# Nusbio_2-MCU-EX.net
KiCad netlist of a schematic drawn in EAGLE
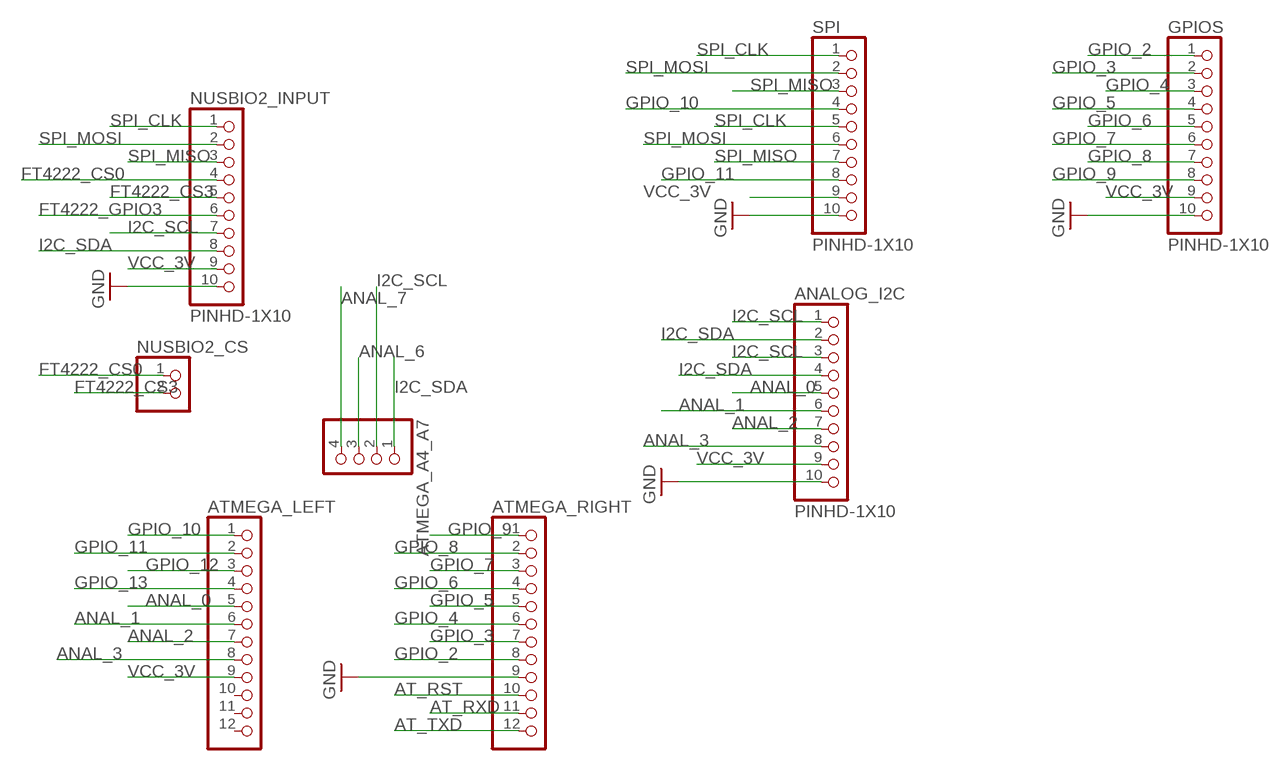
[diagram p0: schematic, sheet 1]

(export (version "E")
  (design (tool "Eeschema 10.0.6"))
  (components
    (comp (ref "ANALOG_I2C")
      (value "PINHD-1X10")
      (footprint "eagle-import:1X10-BIG")
      (libsource (lib "eagle-import") (part "PINHD-1X10"))
    )
    (comp (ref "ATMEGA_A4_A7")
      (value "PINHD-1X4")
      (footprint "eagle-import:1X04")
      (libsource (lib "eagle-import") (part "PINHD-1X4"))
    )
    (comp (ref "ATMEGA_LEFT")
      (value "PINHD-1X12")
      (footprint "eagle-import:1X12")
      (libsource (lib "eagle-import") (part "PINHD-1X12"))
    )
    (comp (ref "ATMEGA_RIGHT")
      (value "PINHD-1X12")
      (footprint "eagle-import:1X12")
      (libsource (lib "eagle-import") (part "PINHD-1X12"))
    )
    (comp (ref "GPIOS")
      (value "PINHD-1X10")
      (footprint "eagle-import:1X10-BIG")
      (libsource (lib "eagle-import") (part "PINHD-1X10"))
    )
    (comp (ref "NUSBIO2_CS")
      (value "PINHD-1X2")
      (footprint "eagle-import:1X02")
      (libsource (lib "eagle-import") (part "PINHD-1X2"))
    )
    (comp (ref "NUSBIO2_INPUT")
      (value "PINHD-1X10")
      (footprint "eagle-import:1X10-BIG")
      (libsource (lib "eagle-import") (part "PINHD-1X10"))
    )
    (comp (ref "SPI")
      (value "PINHD-1X10")
      (footprint "eagle-import:1X10-BIG")
      (libsource (lib "eagle-import") (part "PINHD-1X10"))
    )
  )
  (nets
    (net (code "1") (name "/ANAL_0") (class "Default")
      (node (ref "ANALOG_I2C") (pin "5") (pinfunction "5_5") (pintype "passive"))
      (node (ref "ATMEGA_LEFT") (pin "5") (pinfunction "5_5") (pintype "passive"))
    )
    (net (code "2") (name "/ANAL_1") (class "Default")
      (node (ref "ANALOG_I2C") (pin "6") (pinfunction "6_6") (pintype "passive"))
      (node (ref "ATMEGA_LEFT") (pin "6") (pinfunction "6_6") (pintype "passive"))
    )
    (net (code "3") (name "/ANAL_2") (class "Default")
      (node (ref "ANALOG_I2C") (pin "7") (pinfunction "7_7") (pintype "passive"))
      (node (ref "ATMEGA_LEFT") (pin "7") (pinfunction "7_7") (pintype "passive"))
    )
    (net (code "4") (name "/ANAL_3") (class "Default")
      (node (ref "ANALOG_I2C") (pin "8") (pinfunction "8_8") (pintype "passive"))
      (node (ref "ATMEGA_LEFT") (pin "8") (pinfunction "8_8") (pintype "passive"))
    )
    (net (code "5") (name "/ANAL_6") (class "Default")
      (node (ref "ATMEGA_A4_A7") (pin "3") (pinfunction "3_3") (pintype "passive"))
    )
    (net (code "6") (name "/ANAL_7") (class "Default")
      (node (ref "ATMEGA_A4_A7") (pin "4") (pinfunction "4_4") (pintype "passive"))
    )
    (net (code "7") (name "/AT_RST") (class "Default")
      (node (ref "ATMEGA_RIGHT") (pin "10") (pinfunction "10_10") (pintype "passive"))
    )
    (net (code "8") (name "/AT_RXD") (class "Default")
      (node (ref "ATMEGA_RIGHT") (pin "11") (pinfunction "11_11") (pintype "passive"))
    )
    (net (code "9") (name "/AT_TXD") (class "Default")
      (node (ref "ATMEGA_RIGHT") (pin "12") (pinfunction "12_12") (pintype "passive"))
    )
    (net (code "10") (name "/FT4222_CS0") (class "Default")
      (node (ref "NUSBIO2_CS") (pin "1") (pinfunction "1_1") (pintype "passive"))
      (node (ref "NUSBIO2_INPUT") (pin "4") (pinfunction "4_4") (pintype "passive"))
    )
    (net (code "11") (name "/FT4222_CS3") (class "Default")
      (node (ref "NUSBIO2_CS") (pin "2") (pinfunction "2_2") (pintype "passive"))
      (node (ref "NUSBIO2_INPUT") (pin "5") (pinfunction "5_5") (pintype "passive"))
    )
    (net (code "12") (name "/FT4222_GPIO3") (class "Default")
      (node (ref "NUSBIO2_INPUT") (pin "6") (pinfunction "6_6") (pintype "passive"))
    )
    (net (code "13") (name "/GPIO_2") (class "Default")
      (node (ref "ATMEGA_RIGHT") (pin "8") (pinfunction "8_8") (pintype "passive"))
      (node (ref "GPIOS") (pin "1") (pinfunction "1_1") (pintype "passive"))
    )
    (net (code "14") (name "/GPIO_3") (class "Default")
      (node (ref "ATMEGA_RIGHT") (pin "7") (pinfunction "7_7") (pintype "passive"))
      (node (ref "GPIOS") (pin "2") (pinfunction "2_2") (pintype "passive"))
    )
    (net (code "15") (name "/GPIO_4") (class "Default")
      (node (ref "ATMEGA_RIGHT") (pin "6") (pinfunction "6_6") (pintype "passive"))
      (node (ref "GPIOS") (pin "3") (pinfunction "3_3") (pintype "passive"))
    )
    (net (code "16") (name "/GPIO_5") (class "Default")
      (node (ref "ATMEGA_RIGHT") (pin "5") (pinfunction "5_5") (pintype "passive"))
      (node (ref "GPIOS") (pin "4") (pinfunction "4_4") (pintype "passive"))
    )
    (net (code "17") (name "/GPIO_6") (class "Default")
      (node (ref "ATMEGA_RIGHT") (pin "4") (pinfunction "4_4") (pintype "passive"))
      (node (ref "GPIOS") (pin "5") (pinfunction "5_5") (pintype "passive"))
    )
    (net (code "18") (name "/GPIO_7") (class "Default")
      (node (ref "ATMEGA_RIGHT") (pin "3") (pinfunction "3_3") (pintype "passive"))
      (node (ref "GPIOS") (pin "6") (pinfunction "6_6") (pintype "passive"))
    )
    (net (code "19") (name "/GPIO_8") (class "Default")
      (node (ref "ATMEGA_RIGHT") (pin "2") (pinfunction "2_2") (pintype "passive"))
      (node (ref "GPIOS") (pin "7") (pinfunction "7_7") (pintype "passive"))
    )
    (net (code "20") (name "/GPIO_9") (class "Default")
      (node (ref "ATMEGA_RIGHT") (pin "1") (pinfunction "1_1") (pintype "passive"))
      (node (ref "GPIOS") (pin "8") (pinfunction "8_8") (pintype "passive"))
    )
    (net (code "21") (name "/GPIO_10") (class "Default")
      (node (ref "ATMEGA_LEFT") (pin "1") (pinfunction "1_1") (pintype "passive"))
      (node (ref "SPI") (pin "4") (pinfunction "4_4") (pintype "passive"))
    )
    (net (code "22") (name "/GPIO_11") (class "Default")
      (node (ref "ATMEGA_LEFT") (pin "2") (pinfunction "2_2") (pintype "passive"))
      (node (ref "SPI") (pin "8") (pinfunction "8_8") (pintype "passive"))
    )
    (net (code "23") (name "/GPIO_12") (class "Default")
      (node (ref "ATMEGA_LEFT") (pin "3") (pinfunction "3_3") (pintype "passive"))
    )
    (net (code "24") (name "/GPIO_13") (class "Default")
      (node (ref "ATMEGA_LEFT") (pin "4") (pinfunction "4_4") (pintype "passive"))
    )
    (net (code "25") (name "/I2C_SCL") (class "Default")
      (node (ref "ANALOG_I2C") (pin "1") (pinfunction "1_1") (pintype "passive"))
      (node (ref "ANALOG_I2C") (pin "3") (pinfunction "3_3") (pintype "passive"))
      (node (ref "ATMEGA_A4_A7") (pin "2") (pinfunction "2_2") (pintype "passive"))
      (node (ref "NUSBIO2_INPUT") (pin "7") (pinfunction "7_7") (pintype "passive"))
    )
    (net (code "26") (name "/I2C_SDA") (class "Default")
      (node (ref "ANALOG_I2C") (pin "2") (pinfunction "2_2") (pintype "passive"))
      (node (ref "ANALOG_I2C") (pin "4") (pinfunction "4_4") (pintype "passive"))
      (node (ref "ATMEGA_A4_A7") (pin "1") (pinfunction "1_1") (pintype "passive"))
      (node (ref "NUSBIO2_INPUT") (pin "8") (pinfunction "8_8") (pintype "passive"))
    )
    (net (code "27") (name "/SPI_CLK") (class "Default")
      (node (ref "NUSBIO2_INPUT") (pin "1") (pinfunction "1_1") (pintype "passive"))
      (node (ref "SPI") (pin "1") (pinfunction "1_1") (pintype "passive"))
      (node (ref "SPI") (pin "5") (pinfunction "5_5") (pintype "passive"))
    )
    (net (code "28") (name "/SPI_MISO") (class "Default")
      (node (ref "NUSBIO2_INPUT") (pin "3") (pinfunction "3_3") (pintype "passive"))
      (node (ref "SPI") (pin "3") (pinfunction "3_3") (pintype "passive"))
      (node (ref "SPI") (pin "7") (pinfunction "7_7") (pintype "passive"))
    )
    (net (code "29") (name "/SPI_MOSI") (class "Default")
      (node (ref "NUSBIO2_INPUT") (pin "2") (pinfunction "2_2") (pintype "passive"))
      (node (ref "SPI") (pin "2") (pinfunction "2_2") (pintype "passive"))
      (node (ref "SPI") (pin "6") (pinfunction "6_6") (pintype "passive"))
    )
    (net (code "30") (name "/VCC_3V") (class "Default")
      (node (ref "ANALOG_I2C") (pin "9") (pinfunction "9_9") (pintype "passive"))
      (node (ref "ATMEGA_LEFT") (pin "9") (pinfunction "9_9") (pintype "passive"))
      (node (ref "GPIOS") (pin "9") (pinfunction "9_9") (pintype "passive"))
      (node (ref "NUSBIO2_INPUT") (pin "9") (pinfunction "9_9") (pintype "passive"))
      (node (ref "SPI") (pin "9") (pinfunction "9_9") (pintype "passive"))
    )
    (net (code "31") (name "GND") (class "Default")
      (node (ref "ANALOG_I2C") (pin "10") (pinfunction "10_10") (pintype "passive"))
      (node (ref "ATMEGA_RIGHT") (pin "9") (pinfunction "9_9") (pintype "passive"))
      (node (ref "GPIOS") (pin "10") (pinfunction "10_10") (pintype "passive"))
      (node (ref "NUSBIO2_INPUT") (pin "10") (pinfunction "10_10") (pintype "passive"))
      (node (ref "SPI") (pin "10") (pinfunction "10_10") (pintype "passive"))
    )
    (net (code "32") (name "unconnected-(ATMEGA_LEFT-Pad10)") (class "Default")
      (node (ref "ATMEGA_LEFT") (pin "10") (pinfunction "10_10") (pintype "passive"))
    )
    (net (code "33") (name "unconnected-(ATMEGA_LEFT-Pad11)") (class "Default")
      (node (ref "ATMEGA_LEFT") (pin "11") (pinfunction "11_11") (pintype "passive"))
    )
    (net (code "34") (name "unconnected-(ATMEGA_LEFT-Pad12)") (class "Default")
      (node (ref "ATMEGA_LEFT") (pin "12") (pinfunction "12_12") (pintype "passive"))
    )
  )
)
